# Converter.net
KiCad netlist of a schematic drawn in Altium Designer
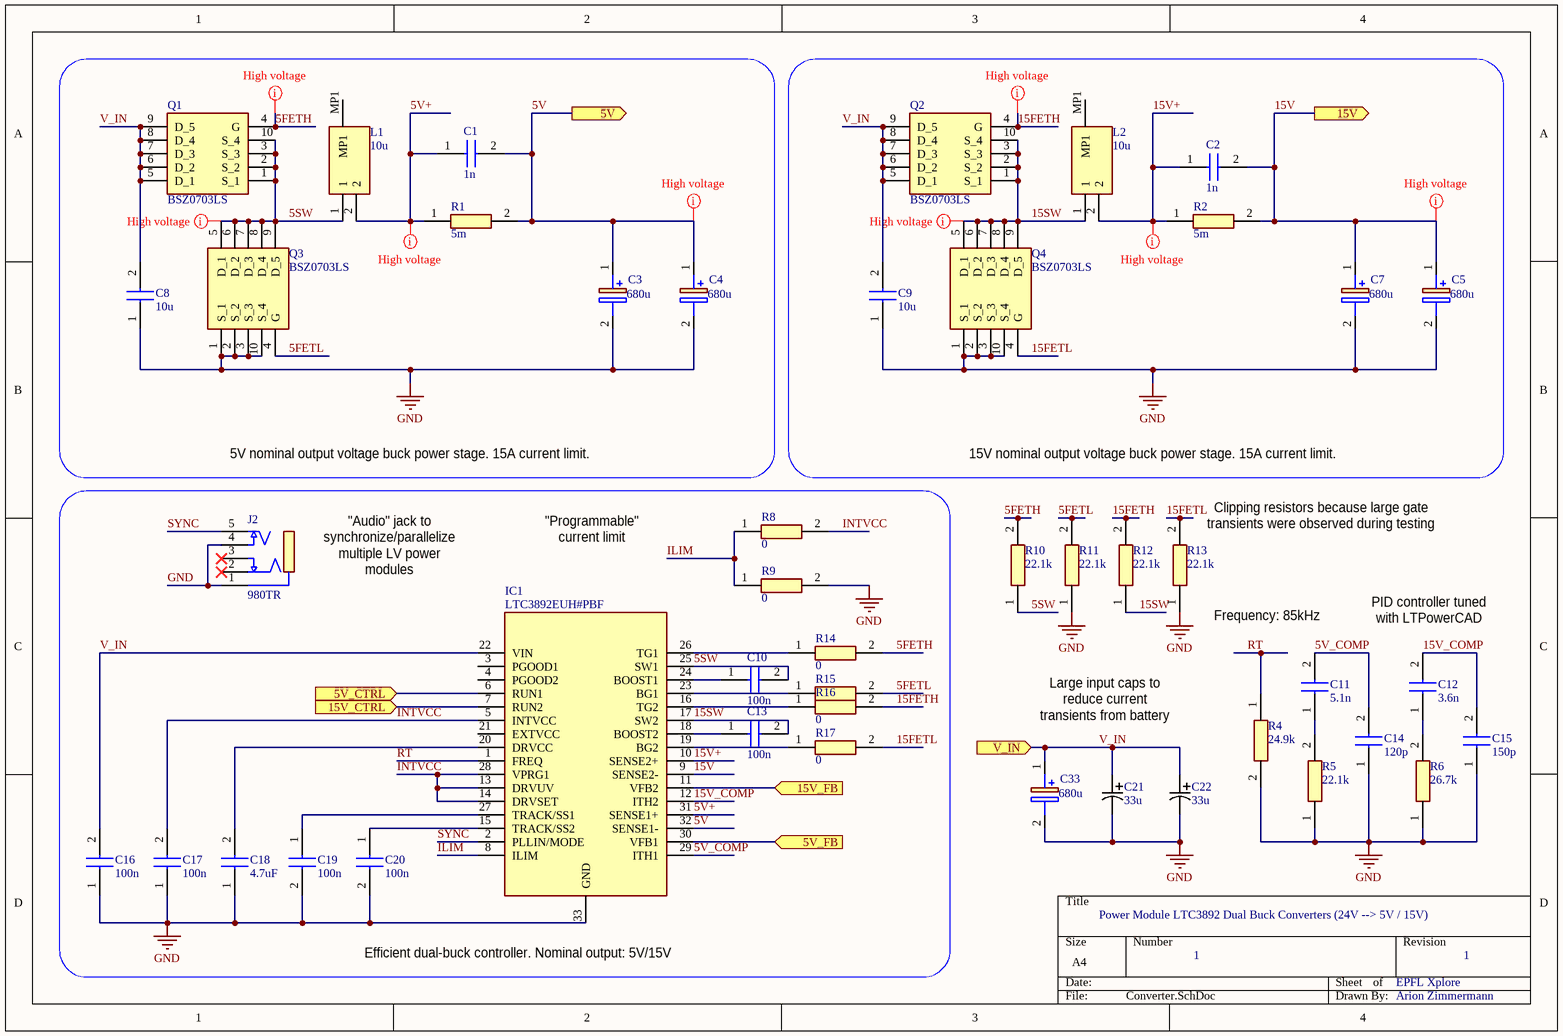
[diagram p0: Converter.SchDoc]

(export (version "E")
  (design (tool "Eeschema 10.0.6"))
  (components
    (comp (ref "C1")
      (value "1n")
      (footprint "SamacSys:CAPC1608X95N")
      (description "Capacitor")
      (fields
        (field (name "MANUFACTURER_PART_NUMBER") "C0603C104K5RACTU")
        (field (name "MOUSER PART NUMBER") "80-C0603C104K5R")
      )
      (libsource (lib "*") (part "C0603C104K5RACTU"))
    )
    (comp (ref "C2")
      (value "1n")
      (footprint "SamacSys:CAPC1608X95N")
      (description "Capacitor")
      (fields
        (field (name "MANUFACTURER_PART_NUMBER") "C0603C104K5RACTU")
        (field (name "MOUSER PART NUMBER") "80-C0603C104K5R")
      )
      (libsource (lib "*") (part "C0603C104K5RACTU"))
    )
    (comp (ref "C3")
      (value "680u")
      (footprint "SamacSys:CAPPRD500W65D1000H1800")
      (description "Capacitor Polarised")
      (fields (field (name "MANUFACTURER_PART_NUMBER") "A750MW687M1VAAE018"))
      (libsource (lib "SamacSys") (part "A750MW687M1VAAE018"))
    )
    (comp (ref "C4")
      (value "680u")
      (footprint "SamacSys:CAPPRD500W65D1000H1800")
      (description "Capacitor Polarised")
      (fields (field (name "MANUFACTURER_PART_NUMBER") "A750MW687M1VAAE018"))
      (libsource (lib "SamacSys") (part "A750MW687M1VAAE018"))
    )
    (comp (ref "C5")
      (value "680u")
      (footprint "SamacSys:CAPPRD500W65D1000H1800")
      (description "Capacitor Polarised")
      (fields (field (name "MANUFACTURER_PART_NUMBER") "A750MW687M1VAAE018"))
      (libsource (lib "SamacSys") (part "A750MW687M1VAAE018"))
    )
    (comp (ref "C7")
      (value "680u")
      (footprint "SamacSys:CAPPRD500W65D1000H1800")
      (description "Capacitor Polarised")
      (fields (field (name "MANUFACTURER_PART_NUMBER") "A750MW687M1VAAE018"))
      (libsource (lib "SamacSys") (part "A750MW687M1VAAE018"))
    )
    (comp (ref "C8")
      (value "10u")
      (footprint "SamacSys:CAPC5750X310N")
      (description "Capacitor")
      (fields
        (field (name "MANUFACTURER_PART_NUMBER") "C5750X7S2A106K230KB")
        (field (name "MOUSER PART NUMBER") "810-C5750X7S2A106KKB")
      )
      (libsource (lib "SamacSys") (part "C5750X7S2A106K230KB"))
    )
    (comp (ref "C9")
      (value "10u")
      (footprint "SamacSys:CAPC5750X310N")
      (description "Capacitor")
      (fields
        (field (name "MANUFACTURER_PART_NUMBER") "C5750X7S2A106K230KB")
        (field (name "MOUSER PART NUMBER") "810-C5750X7S2A106KKB")
      )
      (libsource (lib "SamacSys") (part "C5750X7S2A106K230KB"))
    )
    (comp (ref "C10")
      (value "100n")
      (footprint "SamacSys:CAPC1608X95N")
      (description "Capacitor")
      (fields
        (field (name "MANUFACTURER_PART_NUMBER") "C0603C104K5RACTU")
        (field (name "MOUSER PART NUMBER") "80-C0603C104K5R")
      )
      (libsource (lib "*") (part "C0603C104K5RACTU"))
    )
    (comp (ref "C11")
      (value "5.1n")
      (footprint "SamacSys:CAPC1608X87N")
      (description "Capacitor")
      (fields
        (field (name "MANUFACTURER_PART_NUMBER") "C0603C222J5RACAUTO")
        (field (name "MOUSER PART NUMBER") "80-C0603C222J5RAUTO")
      )
      (libsource (lib "*") (part "C0603C222J5RACAUTO"))
    )
    (comp (ref "C12")
      (value "3.6n")
      (footprint "SamacSys:CAPC1608X87N")
      (description "Capacitor")
      (fields
        (field (name "MANUFACTURER_PART_NUMBER") "C0603C102J5RACTU")
        (field (name "MOUSER PART NUMBER") "80-C0603C102J5R")
      )
      (libsource (lib "*") (part "C0603C102J5RACTU"))
    )
    (comp (ref "C13")
      (value "100n")
      (footprint "SamacSys:CAPC1608X95N")
      (description "Capacitor")
      (fields
        (field (name "MANUFACTURER_PART_NUMBER") "C0603C104K5RACTU")
        (field (name "MOUSER PART NUMBER") "80-C0603C104K5R")
      )
      (libsource (lib "*") (part "C0603C104K5RACTU"))
    )
    (comp (ref "C14")
      (value "120p")
      (footprint "SamacSys:CAPC1608X87N")
      (description "Capacitor")
      (fields
        (field (name "MANUFACTURER_PART_NUMBER") "C0603C101J5RACTU")
        (field (name "MOUSER PART NUMBER") "80-C0603C101J5R")
      )
      (libsource (lib "*") (part "C0603C101J5RACTU"))
    )
    (comp (ref "C15")
      (value "150p")
      (footprint "SamacSys:CAPC1608X87N")
      (description "Capacitor")
      (fields
        (field (name "MANUFACTURER_PART_NUMBER") "C0603C101J5RACTU")
        (field (name "MOUSER PART NUMBER") "80-C0603C101J5R")
      )
      (libsource (lib "*") (part "C0603C101J5RACTU"))
    )
    (comp (ref "C16")
      (value "100n")
      (footprint "SamacSys:CAPC1608X95N")
      (description "Capacitor")
      (fields
        (field (name "MANUFACTURER_PART_NUMBER") "C0603C104K5RACTU")
        (field (name "MOUSER PART NUMBER") "80-C0603C104K5R")
      )
      (libsource (lib "*") (part "C0603C104K5RACTU"))
    )
    (comp (ref "C17")
      (value "100n")
      (footprint "SamacSys:CAPC1608X95N")
      (description "Capacitor")
      (fields
        (field (name "MANUFACTURER_PART_NUMBER") "C0603C104K5RACTU")
        (field (name "MOUSER PART NUMBER") "80-C0603C104K5R")
      )
      (libsource (lib "*") (part "C0603C104K5RACTU"))
    )
    (comp (ref "C18")
      (value "4.7uF")
      (footprint "SamacSys:CAPC3316X195N")
      (description "Capacitor")
      (fields
        (field (name "MANUFACTURER_PART_NUMBER") "C1206X475M5RACAUTO")
        (field (name "MOUSER PART NUMBER") "80-C1206X475M5RAUTO")
      )
      (libsource (lib "*") (part "C1206X475M5RACAUTO"))
    )
    (comp (ref "C19")
      (value "100n")
      (footprint "SamacSys:CAPC1608X95N")
      (description "Capacitor")
      (fields
        (field (name "MANUFACTURER_PART_NUMBER") "C0603C104K5RACTU")
        (field (name "MOUSER PART NUMBER") "80-C0603C104K5R")
      )
      (libsource (lib "*") (part "C0603C104K5RACTU"))
    )
    (comp (ref "C20")
      (value "100n")
      (footprint "SamacSys:CAPC1608X95N")
      (description "Capacitor")
      (fields
        (field (name "MANUFACTURER_PART_NUMBER") "C0603C104K5RACTU")
        (field (name "MOUSER PART NUMBER") "80-C0603C104K5R")
      )
      (libsource (lib "*") (part "C0603C104K5RACTU"))
    )
    (comp (ref "C21")
      (value "33u")
      (footprint "CAPMP7.6X4.3_3.1N_KEM")
      (description "No Description Available")
      (fields
        (field (name "MANUFACTURER_PART_NUMBER") "T598D336M035ATE065")
        (field (name "COPYRIGHT") "Copyright (C) 2018 Accelerated Designs. All rights reserved")
      )
      (libsource (lib "2021-05-11_14-36-17") (part "T598D336M035ATE065"))
    )
    (comp (ref "C22")
      (value "33u")
      (footprint "CAPMP7.6X4.3_3.1N_KEM")
      (description "No Description Available")
      (fields
        (field (name "MANUFACTURER_PART_NUMBER") "T598D336M035ATE065")
        (field (name "COPYRIGHT") "Copyright (C) 2018 Accelerated Designs. All rights reserved")
      )
      (libsource (lib "2021-05-11_14-36-17") (part "T598D336M035ATE065"))
    )
    (comp (ref "C33")
      (value "680u")
      (footprint "SamacSys:CAPPRD500W65D1000H1800")
      (description "Capacitor Polarised")
      (fields (field (name "MANUFACTURER_PART_NUMBER") "A750MW687M1VAAE018"))
      (libsource (lib "SamacSys") (part "A750MW687M1VAAE018"))
    )
    (comp (ref "IC1")
      (value "LTC3892EUH#PBF")
      (footprint "SamacSys:QFN50P500X500X80-33N-D")
      (description "Integrated Circuit")
      (libsource (lib "*") (part "LTC3892EUH#PBF"))
    )
    (comp (ref "J2")
      (value "980TR")
      (footprint "SamacSys:980TR")
      (description "Connector")
      (fields (field (name "MOUSER PART NUMBER") "534-980"))
      (libsource (lib "*") (part "980TR"))
    )
    (comp (ref "L1")
      (value "10u")
      (footprint "SamacSys:PQ2614BLA1R0K")
      (description "Inductor")
      (fields
        (field (name "MANUFACTURER_PART_NUMBER") "PQ2614BHA-100K")
        (field (name "MOUSER PART NUMBER") "652-PQ2614BHA-100K")
      )
      (libsource (lib "*") (part "PQ2614BHA-100K"))
    )
    (comp (ref "L2")
      (value "10u")
      (footprint "SamacSys:PQ2614BLA1R0K")
      (description "Inductor")
      (fields
        (field (name "MANUFACTURER_PART_NUMBER") "PQ2614BHA-100K")
        (field (name "MOUSER PART NUMBER") "652-PQ2614BHA-100K")
      )
      (libsource (lib "*") (part "PQ2614BHA-100K"))
    )
    (comp (ref "Q1")
      (value "BSZ0703LS")
      (footprint "SamacSys:BSZ011NE2LS5IATMA1")
      (description "MOSFET (N-Channel)")
      (fields
        (field (name "MANUFACTURER_PART_NUMBER") "BSZ011NE2LS5IATMA1")
        (field (name "MOUSER PART NUMBER") "726-BSZ011NE2LS5IATM")
      )
      (libsource (lib "") (part "BSZ011NE2LS5IATMA1_1"))
    )
    (comp (ref "Q2")
      (value "BSZ0703LS")
      (footprint "SamacSys:BSZ011NE2LS5IATMA1")
      (description "MOSFET (N-Channel)")
      (fields
        (field (name "MANUFACTURER_PART_NUMBER") "BSZ011NE2LS5IATMA1")
        (field (name "MOUSER PART NUMBER") "726-BSZ011NE2LS5IATM")
      )
      (libsource (lib "") (part "BSZ011NE2LS5IATMA1_1"))
    )
    (comp (ref "Q3")
      (value "BSZ0703LS")
      (footprint "SamacSys:BSZ011NE2LS5IATMA1")
      (description "MOSFET (N-Channel)")
      (fields
        (field (name "MANUFACTURER_PART_NUMBER") "BSZ011NE2LS5IATMA1")
        (field (name "MOUSER PART NUMBER") "726-BSZ011NE2LS5IATM")
      )
      (libsource (lib "*") (part "BSZ011NE2LS5IATMA1"))
    )
    (comp (ref "Q4")
      (value "BSZ0703LS")
      (footprint "SamacSys:BSZ011NE2LS5IATMA1")
      (description "MOSFET (N-Channel)")
      (fields
        (field (name "MANUFACTURER_PART_NUMBER") "BSZ011NE2LS5IATMA1")
        (field (name "MOUSER PART NUMBER") "726-BSZ011NE2LS5IATM")
      )
      (libsource (lib "*") (part "BSZ011NE2LS5IATMA1"))
    )
    (comp (ref "R1")
      (value "5m")
      (footprint "SamacSys:RESC6432X80N")
      (description "Resistor")
      (fields
        (field (name "MANUFACTURER_PART_NUMBER") "CRF2512-FZ-R005ELF")
        (field (name "MOUSER PART NUMBER") "652-CRF2512FZR005ELF")
      )
      (libsource (lib "*") (part "CRF2512-FZ-R005ELF"))
    )
    (comp (ref "R2")
      (value "5m")
      (footprint "SamacSys:RESC6432X80N")
      (description "Resistor")
      (fields
        (field (name "MANUFACTURER_PART_NUMBER") "CRF2512-FZ-R005ELF")
        (field (name "MOUSER PART NUMBER") "652-CRF2512FZR005ELF")
      )
      (libsource (lib "*") (part "CRF2512-FZ-R005ELF"))
    )
    (comp (ref "R4")
      (value "24.9k")
      (footprint "SamacSys:RESC1608X50N")
      (description "Resistor")
      (fields
        (field (name "MANUFACTURER_PART_NUMBER") "CRCW060324K9FKEA")
        (field (name "MOUSER PART NUMBER") "71-CRCW0603-24.9K-E3")
      )
      (libsource (lib "*") (part "CRCW060324K9FKEA"))
    )
    (comp (ref "R5")
      (value "22.1k")
      (footprint "SamacSys:RESC1608X50N")
      (description "Resistor")
      (fields
        (field (name "MANUFACTURER_PART_NUMBER") "CRCW06037K50FKEB")
        (field (name "MOUSER PART NUMBER") "71-CRCW06037K50FKEB")
      )
      (libsource (lib "*") (part "CRCW06037K50FKEB"))
    )
    (comp (ref "R6")
      (value "26.7k")
      (footprint "SamacSys:RESC1608X50N")
      (description "Resistor")
      (fields
        (field (name "MANUFACTURER_PART_NUMBER") "CRCW060334K0FKEA")
        (field (name "MOUSER PART NUMBER") "71-CRCW0603-34K-E3")
      )
      (libsource (lib "*") (part "CRCW060334K0FKEA"))
    )
    (comp (ref "R8")
      (value "CRCW06030000ZSTB")
      (footprint "SamacSys:RESC1608X50N")
      (description "Resistor")
      (fields (field (name "MOUSER PART NUMBER") "71-CRCW0603000ZT-RT5") (field (name "PARAMETER 1") "0"))
      (libsource (lib "*") (part "CRCW06030000ZSTB"))
    )
    (comp (ref "R9")
      (value "CRCW06030000ZSTB")
      (footprint "SamacSys:RESC1608X50N")
      (description "Resistor")
      (fields (field (name "MOUSER PART NUMBER") "71-CRCW0603000ZT-RT5") (field (name "PARAMETER 1") "0"))
      (libsource (lib "*") (part "CRCW06030000ZSTB"))
    )
    (comp (ref "R10")
      (value "22.1k")
      (footprint "SamacSys:RESC1608X50N")
      (description "Resistor")
      (fields
        (field (name "MANUFACTURER_PART_NUMBER") "CRCW06037K50FKEB")
        (field (name "MOUSER PART NUMBER") "71-CRCW06037K50FKEB")
      )
      (libsource (lib "*") (part "CRCW06037K50FKEB"))
    )
    (comp (ref "R11")
      (value "22.1k")
      (footprint "SamacSys:RESC1608X50N")
      (description "Resistor")
      (fields
        (field (name "MANUFACTURER_PART_NUMBER") "CRCW06037K50FKEB")
        (field (name "MOUSER PART NUMBER") "71-CRCW06037K50FKEB")
      )
      (libsource (lib "*") (part "CRCW06037K50FKEB"))
    )
    (comp (ref "R12")
      (value "22.1k")
      (footprint "SamacSys:RESC1608X50N")
      (description "Resistor")
      (fields
        (field (name "MANUFACTURER_PART_NUMBER") "CRCW06037K50FKEB")
        (field (name "MOUSER PART NUMBER") "71-CRCW06037K50FKEB")
      )
      (libsource (lib "*") (part "CRCW06037K50FKEB"))
    )
    (comp (ref "R13")
      (value "22.1k")
      (footprint "SamacSys:RESC1608X50N")
      (description "Resistor")
      (fields
        (field (name "MANUFACTURER_PART_NUMBER") "CRCW06037K50FKEB")
        (field (name "MOUSER PART NUMBER") "71-CRCW06037K50FKEB")
      )
      (libsource (lib "*") (part "CRCW06037K50FKEB"))
    )
    (comp (ref "R14")
      (value "CRCW06030000ZSTB")
      (footprint "SamacSys:RESC1608X50N")
      (description "Resistor")
      (fields (field (name "MOUSER PART NUMBER") "71-CRCW0603000ZT-RT5") (field (name "PARAMETER 1") "0"))
      (libsource (lib "*") (part "CRCW06030000ZSTB"))
    )
    (comp (ref "R15")
      (value "CRCW06030000ZSTB")
      (footprint "SamacSys:RESC1608X50N")
      (description "Resistor")
      (fields (field (name "MOUSER PART NUMBER") "71-CRCW0603000ZT-RT5") (field (name "PARAMETER 1") "0"))
      (libsource (lib "*") (part "CRCW06030000ZSTB"))
    )
    (comp (ref "R16")
      (value "CRCW06030000ZSTB")
      (footprint "SamacSys:RESC1608X50N")
      (description "Resistor")
      (fields (field (name "MOUSER PART NUMBER") "71-CRCW0603000ZT-RT5") (field (name "PARAMETER 1") "0"))
      (libsource (lib "*") (part "CRCW06030000ZSTB"))
    )
    (comp (ref "R17")
      (value "CRCW06030000ZSTB")
      (footprint "SamacSys:RESC1608X50N")
      (description "Resistor")
      (fields (field (name "MOUSER PART NUMBER") "71-CRCW0603000ZT-RT5") (field (name "PARAMETER 1") "0"))
      (libsource (lib "*") (part "CRCW06030000ZSTB"))
    )
  )
  (nets
    (net (code "1") (name "/5FETH") (class "Default")
      (node (ref "Q1") (pin "4") (pinfunction "G_4") (pintype "passive"))
      (node (ref "R10") (pin "2") (pinfunction "2_2") (pintype "passive"))
      (node (ref "R14") (pin "2") (pinfunction "2_2") (pintype "passive"))
    )
    (net (code "2") (name "/5FETL") (class "Default")
      (node (ref "Q3") (pin "4") (pinfunction "G_4") (pintype "passive"))
      (node (ref "R11") (pin "2") (pinfunction "2_2") (pintype "passive"))
      (node (ref "R15") (pin "2") (pinfunction "2_2") (pintype "passive"))
    )
    (net (code "3") (name "/5SW") (class "Default")
      (node (ref "C10") (pin "2") (pinfunction "2_2") (pintype "passive"))
      (node (ref "IC1") (pin "25") (pinfunction "SW1_25") (pintype "passive"))
      (node (ref "L1") (pin "1") (pinfunction "1_1") (pintype "passive"))
      (node (ref "Q1") (pin "1") (pinfunction "S_1_1") (pintype "passive"))
      (node (ref "Q1") (pin "10") (pinfunction "S_4_10") (pintype "passive"))
      (node (ref "Q1") (pin "2") (pinfunction "S_2_2") (pintype "passive"))
      (node (ref "Q1") (pin "3") (pinfunction "S_3_3") (pintype "passive"))
      (node (ref "Q3") (pin "5") (pinfunction "D_1_5") (pintype "passive"))
      (node (ref "Q3") (pin "6") (pinfunction "D_2_6") (pintype "passive"))
      (node (ref "Q3") (pin "7") (pinfunction "D_3_7") (pintype "passive"))
      (node (ref "Q3") (pin "8") (pinfunction "D_4_8") (pintype "passive"))
      (node (ref "Q3") (pin "9") (pinfunction "D_5_9") (pintype "passive"))
      (node (ref "R10") (pin "1") (pinfunction "1_1") (pintype "passive"))
    )
    (net (code "4") (name "/5V") (class "Default")
      (node (ref "C1") (pin "2") (pinfunction "2_2") (pintype "passive"))
      (node (ref "C3") (pin "1") (pinfunction "+_1") (pintype "passive"))
      (node (ref "C4") (pin "1") (pinfunction "+_1") (pintype "passive"))
      (node (ref "IC1") (pin "32") (pinfunction "SENSE1-_32") (pintype "passive"))
      (node (ref "R1") (pin "2") (pinfunction "2_2") (pintype "passive"))
    )
    (net (code "5") (name "/5V+") (class "Default")
      (node (ref "C1") (pin "1") (pinfunction "1_1") (pintype "passive"))
      (node (ref "IC1") (pin "31") (pinfunction "SENSE1+_31") (pintype "passive"))
      (node (ref "L1") (pin "2") (pinfunction "2_2") (pintype "passive"))
      (node (ref "R1") (pin "1") (pinfunction "1_1") (pintype "passive"))
    )
    (net (code "6") (name "/5V_COMP") (class "Default")
      (node (ref "C11") (pin "2") (pinfunction "2_2") (pintype "passive"))
      (node (ref "C14") (pin "2") (pinfunction "2_2") (pintype "passive"))
      (node (ref "IC1") (pin "29") (pinfunction "ITH1_29") (pintype "passive"))
    )
    (net (code "7") (name "/5V_CTRL") (class "Default")
      (node (ref "IC1") (pin "6") (pinfunction "RUN1_6") (pintype "passive"))
    )
    (net (code "8") (name "/5V_FB") (class "Default")
      (node (ref "IC1") (pin "30") (pinfunction "VFB1_30") (pintype "passive"))
    )
    (net (code "9") (name "/15FETH") (class "Default")
      (node (ref "Q2") (pin "4") (pinfunction "G_4") (pintype "passive"))
      (node (ref "R12") (pin "2") (pinfunction "2_2") (pintype "passive"))
      (node (ref "R16") (pin "2") (pinfunction "2_2") (pintype "passive"))
    )
    (net (code "10") (name "/15FETL") (class "Default")
      (node (ref "Q4") (pin "4") (pinfunction "G_4") (pintype "passive"))
      (node (ref "R13") (pin "2") (pinfunction "2_2") (pintype "passive"))
      (node (ref "R17") (pin "2") (pinfunction "2_2") (pintype "passive"))
    )
    (net (code "11") (name "/15SW") (class "Default")
      (node (ref "C13") (pin "2") (pinfunction "2_2") (pintype "passive"))
      (node (ref "IC1") (pin "17") (pinfunction "SW2_17") (pintype "passive"))
      (node (ref "L2") (pin "1") (pinfunction "1_1") (pintype "passive"))
      (node (ref "Q2") (pin "1") (pinfunction "S_1_1") (pintype "passive"))
      (node (ref "Q2") (pin "10") (pinfunction "S_4_10") (pintype "passive"))
      (node (ref "Q2") (pin "2") (pinfunction "S_2_2") (pintype "passive"))
      (node (ref "Q2") (pin "3") (pinfunction "S_3_3") (pintype "passive"))
      (node (ref "Q4") (pin "5") (pinfunction "D_1_5") (pintype "passive"))
      (node (ref "Q4") (pin "6") (pinfunction "D_2_6") (pintype "passive"))
      (node (ref "Q4") (pin "7") (pinfunction "D_3_7") (pintype "passive"))
      (node (ref "Q4") (pin "8") (pinfunction "D_4_8") (pintype "passive"))
      (node (ref "Q4") (pin "9") (pinfunction "D_5_9") (pintype "passive"))
      (node (ref "R12") (pin "1") (pinfunction "1_1") (pintype "passive"))
    )
    (net (code "12") (name "/15V") (class "Default")
      (node (ref "C2") (pin "2") (pinfunction "2_2") (pintype "passive"))
      (node (ref "C5") (pin "1") (pinfunction "+_1") (pintype "passive"))
      (node (ref "C7") (pin "1") (pinfunction "+_1") (pintype "passive"))
      (node (ref "IC1") (pin "9") (pinfunction "SENSE2-_9") (pintype "passive"))
      (node (ref "R2") (pin "2") (pinfunction "2_2") (pintype "passive"))
    )
    (net (code "13") (name "/15V+") (class "Default")
      (node (ref "C2") (pin "1") (pinfunction "1_1") (pintype "passive"))
      (node (ref "IC1") (pin "10") (pinfunction "SENSE2+_10") (pintype "passive"))
      (node (ref "L2") (pin "2") (pinfunction "2_2") (pintype "passive"))
      (node (ref "R2") (pin "1") (pinfunction "1_1") (pintype "passive"))
    )
    (net (code "14") (name "/15V_COMP") (class "Default")
      (node (ref "C12") (pin "2") (pinfunction "2_2") (pintype "passive"))
      (node (ref "C15") (pin "2") (pinfunction "2_2") (pintype "passive"))
      (node (ref "IC1") (pin "12") (pinfunction "ITH2_12") (pintype "passive"))
    )
    (net (code "15") (name "/15V_CTRL") (class "Default")
      (node (ref "IC1") (pin "7") (pinfunction "RUN2_7") (pintype "passive"))
    )
    (net (code "16") (name "/15V_FB") (class "Default")
      (node (ref "IC1") (pin "11") (pinfunction "VFB2_11") (pintype "passive"))
    )
    (net (code "17") (name "/ILIM") (class "Default")
      (node (ref "IC1") (pin "8") (pinfunction "ILIM_8") (pintype "passive"))
      (node (ref "R8") (pin "1") (pinfunction "1_1") (pintype "passive"))
      (node (ref "R9") (pin "1") (pinfunction "1_1") (pintype "passive"))
    )
    (net (code "18") (name "/INTVCC") (class "Default")
      (node (ref "C17") (pin "2") (pinfunction "2_2") (pintype "passive"))
      (node (ref "IC1") (pin "13") (pinfunction "DRVUV_13") (pintype "passive"))
      (node (ref "IC1") (pin "14") (pinfunction "DRVSET_14") (pintype "passive"))
      (node (ref "IC1") (pin "28") (pinfunction "VPRG1_28") (pintype "passive"))
      (node (ref "IC1") (pin "5") (pinfunction "INTVCC_5") (pintype "passive"))
      (node (ref "R8") (pin "2") (pinfunction "2_2") (pintype "passive"))
    )
    (net (code "19") (name "/RT") (class "Default")
      (node (ref "IC1") (pin "1") (pinfunction "FREQ_1") (pintype "passive"))
      (node (ref "R4") (pin "1") (pinfunction "1_1") (pintype "passive"))
    )
    (net (code "20") (name "/SYNC") (class "Default")
      (node (ref "IC1") (pin "2") (pinfunction "PLLIN/MODE_2") (pintype "passive"))
      (node (ref "J2") (pin "5") (pinfunction "5_5") (pintype "passive"))
    )
    (net (code "21") (name "/V_IN") (class "Default")
      (node (ref "C16") (pin "2") (pinfunction "2_2") (pintype "passive"))
      (node (ref "C21") (pin "1") (pinfunction "1_1") (pintype "passive"))
      (node (ref "C22") (pin "1") (pinfunction "1_1") (pintype "passive"))
      (node (ref "C33") (pin "1") (pinfunction "+_1") (pintype "passive"))
      (node (ref "C8") (pin "2") (pinfunction "2_2") (pintype "passive"))
      (node (ref "C9") (pin "2") (pinfunction "2_2") (pintype "passive"))
      (node (ref "IC1") (pin "22") (pinfunction "VIN_22") (pintype "passive"))
      (node (ref "Q1") (pin "5") (pinfunction "D_1_5") (pintype "passive"))
      (node (ref "Q1") (pin "6") (pinfunction "D_2_6") (pintype "passive"))
      (node (ref "Q1") (pin "7") (pinfunction "D_3_7") (pintype "passive"))
      (node (ref "Q1") (pin "8") (pinfunction "D_4_8") (pintype "passive"))
      (node (ref "Q1") (pin "9") (pinfunction "D_5_9") (pintype "passive"))
      (node (ref "Q2") (pin "5") (pinfunction "D_1_5") (pintype "passive"))
      (node (ref "Q2") (pin "6") (pinfunction "D_2_6") (pintype "passive"))
      (node (ref "Q2") (pin "7") (pinfunction "D_3_7") (pintype "passive"))
      (node (ref "Q2") (pin "8") (pinfunction "D_4_8") (pintype "passive"))
      (node (ref "Q2") (pin "9") (pinfunction "D_5_9") (pintype "passive"))
    )
    (net (code "22") (name "GND") (class "Default")
      (node (ref "C14") (pin "1") (pinfunction "1_1") (pintype "passive"))
      (node (ref "C15") (pin "1") (pinfunction "1_1") (pintype "passive"))
      (node (ref "C16") (pin "1") (pinfunction "1_1") (pintype "passive"))
      (node (ref "C17") (pin "1") (pinfunction "1_1") (pintype "passive"))
      (node (ref "C18") (pin "1") (pinfunction "1_1") (pintype "passive"))
      (node (ref "C19") (pin "2") (pinfunction "2_2") (pintype "passive"))
      (node (ref "C20") (pin "2") (pinfunction "2_2") (pintype "passive"))
      (node (ref "C21") (pin "2") (pinfunction "2_2") (pintype "passive"))
      (node (ref "C22") (pin "2") (pinfunction "2_2") (pintype "passive"))
      (node (ref "C3") (pin "2") (pinfunction "-_2") (pintype "passive"))
      (node (ref "C33") (pin "2") (pinfunction "-_2") (pintype "passive"))
      (node (ref "C4") (pin "2") (pinfunction "-_2") (pintype "passive"))
      (node (ref "C5") (pin "2") (pinfunction "-_2") (pintype "passive"))
      (node (ref "C7") (pin "2") (pinfunction "-_2") (pintype "passive"))
      (node (ref "C8") (pin "1") (pinfunction "1_1") (pintype "passive"))
      (node (ref "C9") (pin "1") (pinfunction "1_1") (pintype "passive"))
      (node (ref "IC1") (pin "33") (pinfunction "GND_33") (pintype "passive"))
      (node (ref "J2") (pin "1") (pinfunction "1_1") (pintype "passive"))
      (node (ref "J2") (pin "4") (pinfunction "4_4") (pintype "passive"))
      (node (ref "Q3") (pin "1") (pinfunction "S_1_1") (pintype "passive"))
      (node (ref "Q3") (pin "10") (pinfunction "S_4_10") (pintype "passive"))
      (node (ref "Q3") (pin "2") (pinfunction "S_2_2") (pintype "passive"))
      (node (ref "Q3") (pin "3") (pinfunction "S_3_3") (pintype "passive"))
      (node (ref "Q4") (pin "1") (pinfunction "S_1_1") (pintype "passive"))
      (node (ref "Q4") (pin "10") (pinfunction "S_4_10") (pintype "passive"))
      (node (ref "Q4") (pin "2") (pinfunction "S_2_2") (pintype "passive"))
      (node (ref "Q4") (pin "3") (pinfunction "S_3_3") (pintype "passive"))
      (node (ref "R11") (pin "1") (pinfunction "1_1") (pintype "passive"))
      (node (ref "R13") (pin "1") (pinfunction "1_1") (pintype "passive"))
      (node (ref "R4") (pin "2") (pinfunction "2_2") (pintype "passive"))
      (node (ref "R5") (pin "1") (pinfunction "1_1") (pintype "passive"))
      (node (ref "R6") (pin "1") (pinfunction "1_1") (pintype "passive"))
      (node (ref "R9") (pin "2") (pinfunction "2_2") (pintype "passive"))
    )
    (net (code "23") (name "Net-(C11-Pad1)") (class "Default")
      (node (ref "C11") (pin "1") (pinfunction "1_1") (pintype "passive"))
      (node (ref "R5") (pin "2") (pinfunction "2_2") (pintype "passive"))
    )
    (net (code "24") (name "Net-(C12-Pad1)") (class "Default")
      (node (ref "C12") (pin "1") (pinfunction "1_1") (pintype "passive"))
      (node (ref "R6") (pin "2") (pinfunction "2_2") (pintype "passive"))
    )
    (net (code "25") (name "Net-(IC1-BG1)") (class "Default")
      (node (ref "IC1") (pin "23") (pinfunction "BG1_23") (pintype "passive"))
      (node (ref "R15") (pin "1") (pinfunction "1_1") (pintype "passive"))
    )
    (net (code "26") (name "Net-(IC1-BG2)") (class "Default")
      (node (ref "IC1") (pin "19") (pinfunction "BG2_19") (pintype "passive"))
      (node (ref "R17") (pin "1") (pinfunction "1_1") (pintype "passive"))
    )
    (net (code "27") (name "Net-(IC1-BOOST1)") (class "Default")
      (node (ref "C10") (pin "1") (pinfunction "1_1") (pintype "passive"))
      (node (ref "IC1") (pin "24") (pinfunction "BOOST1_24") (pintype "passive"))
    )
    (net (code "28") (name "Net-(IC1-BOOST2)") (class "Default")
      (node (ref "C13") (pin "1") (pinfunction "1_1") (pintype "passive"))
      (node (ref "IC1") (pin "18") (pinfunction "BOOST2_18") (pintype "passive"))
    )
    (net (code "29") (name "Net-(IC1-DRVCC)") (class "Default")
      (node (ref "C18") (pin "2") (pinfunction "2_2") (pintype "passive"))
      (node (ref "IC1") (pin "20") (pinfunction "DRVCC_20") (pintype "passive"))
    )
    (net (code "30") (name "Net-(IC1-TG1)") (class "Default")
      (node (ref "IC1") (pin "26") (pinfunction "TG1_26") (pintype "passive"))
      (node (ref "R14") (pin "1") (pinfunction "1_1") (pintype "passive"))
    )
    (net (code "31") (name "Net-(IC1-TG2)") (class "Default")
      (node (ref "IC1") (pin "16") (pinfunction "TG2_16") (pintype "passive"))
      (node (ref "R16") (pin "1") (pinfunction "1_1") (pintype "passive"))
    )
    (net (code "32") (name "Net-(IC1-TRACK{slash}SS1)") (class "Default")
      (node (ref "C19") (pin "1") (pinfunction "1_1") (pintype "passive"))
      (node (ref "IC1") (pin "27") (pinfunction "TRACK/SS1_27") (pintype "passive"))
    )
    (net (code "33") (name "Net-(IC1-TRACK{slash}SS2)") (class "Default")
      (node (ref "C20") (pin "1") (pinfunction "1_1") (pintype "passive"))
      (node (ref "IC1") (pin "15") (pinfunction "TRACK/SS2_15") (pintype "passive"))
    )
    (net (code "34") (name "unconnected-(IC1-EXTVCC-Pad21)") (class "Default")
      (node (ref "IC1") (pin "21") (pinfunction "EXTVCC_21") (pintype "passive"))
    )
    (net (code "35") (name "unconnected-(IC1-PGOOD1-Pad3)") (class "Default")
      (node (ref "IC1") (pin "3") (pinfunction "PGOOD1_3") (pintype "passive"))
    )
    (net (code "36") (name "unconnected-(IC1-PGOOD2-Pad4)") (class "Default")
      (node (ref "IC1") (pin "4") (pinfunction "PGOOD2_4") (pintype "passive"))
    )
    (net (code "37") (name "unconnected-(J2-Pad2)") (class "Default")
      (node (ref "J2") (pin "2") (pinfunction "2_2") (pintype "passive+no_connect"))
    )
    (net (code "38") (name "unconnected-(J2-Pad3)") (class "Default")
      (node (ref "J2") (pin "3") (pinfunction "3_3") (pintype "passive+no_connect"))
    )
    (net (code "39") (name "unconnected-(L1-PadMP1)") (class "Default")
      (node (ref "L1") (pin "MP1") (pinfunction "MP1_MP1") (pintype "passive"))
    )
    (net (code "40") (name "unconnected-(L2-PadMP1)") (class "Default")
      (node (ref "L2") (pin "MP1") (pinfunction "MP1_MP1") (pintype "passive"))
    )
  )
)
